# Sheet_1_V2_0_2023-09-05.net
KiCad netlist of a schematic drawn in Altium Designer
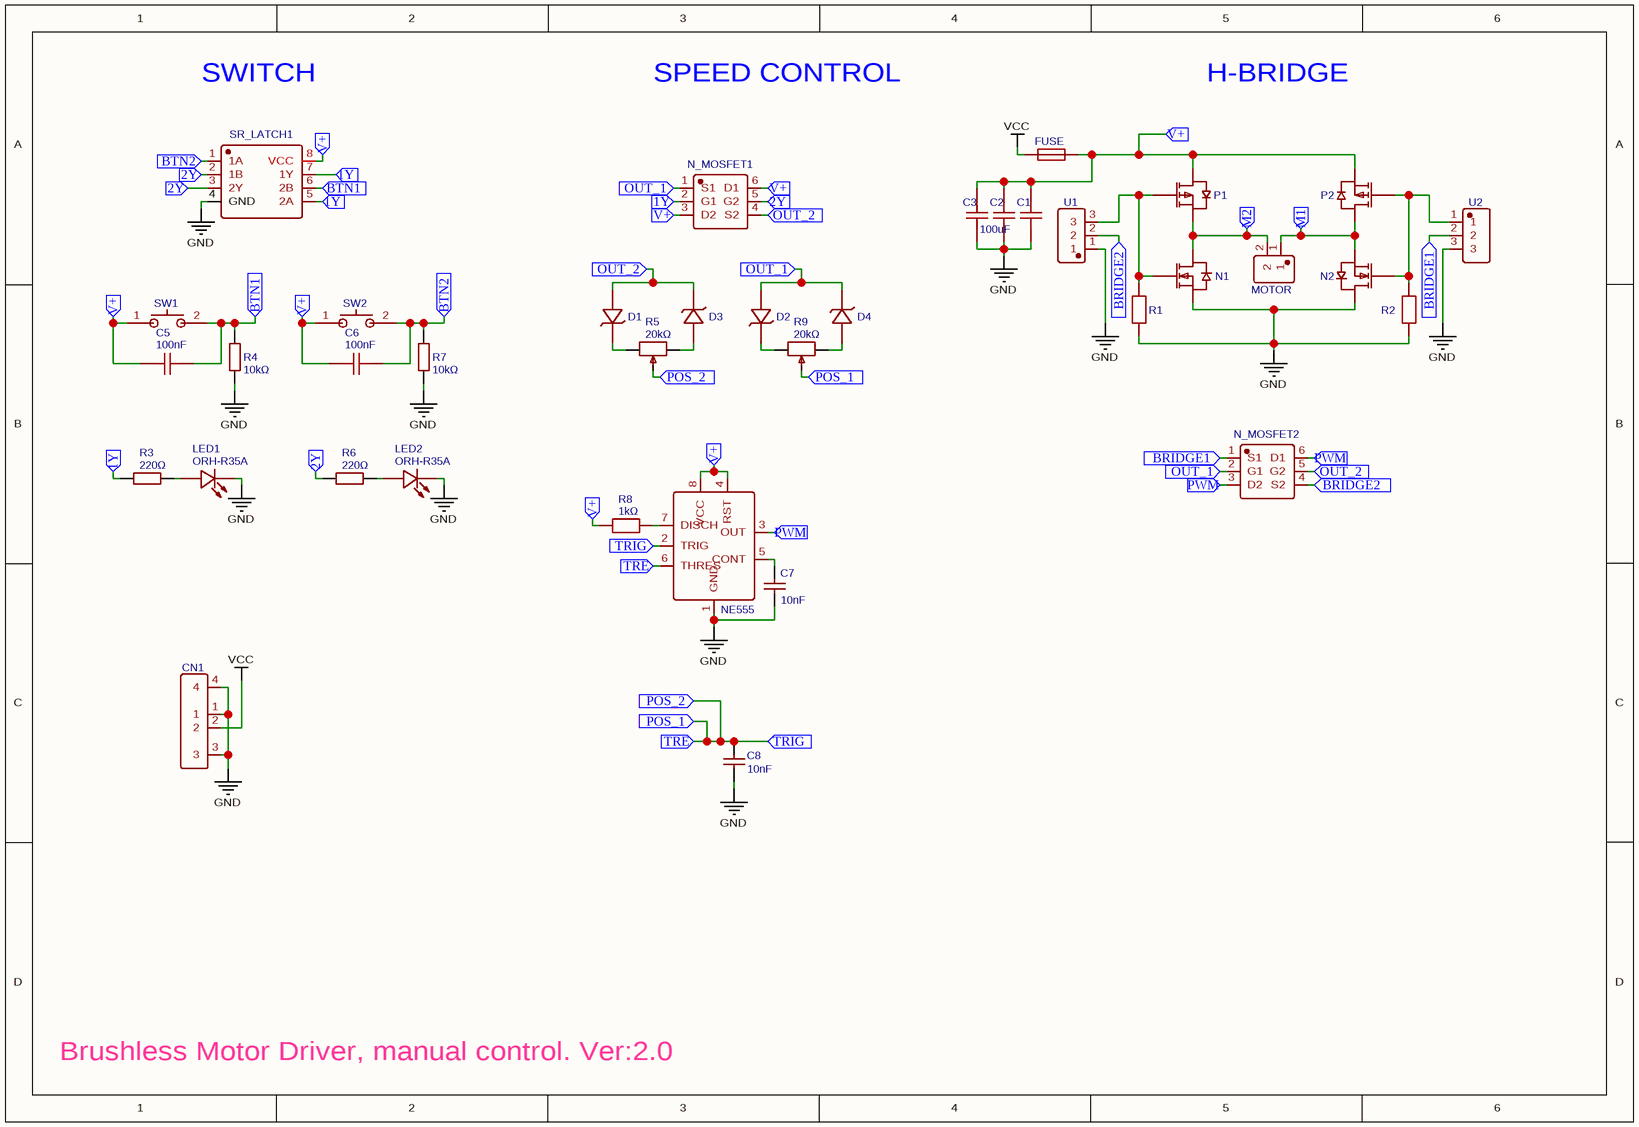
[diagram p0: Sheet_1 V2.0_2023-09-05.schdoc]

(export (version "E")
  (design (tool "Eeschema 10.0.6"))
  (components
    (comp (ref "C1")
      (value "100uF")
      (fields
        (field (name "MANUFACTURER") "muRata(村田)")
        (field (name "MANUFACTURER PART") "GRM31CR61A107MEA8L")
        (field (name "CONTRIBUTOR") "lcsc")
      )
      (libsource (lib "altium-import") (part "root_1_100uF_"))
    )
    (comp (ref "C2")
      (value "100uF")
      (fields
        (field (name "MANUFACTURER") "muRata(村田)")
        (field (name "MANUFACTURER PART") "GRM31CR61A107MEA8L")
        (field (name "CONTRIBUTOR") "lcsc")
      )
      (libsource (lib "altium-import") (part "root_1_100uF_"))
    )
    (comp (ref "C3")
      (value "100uF")
      (fields
        (field (name "MANUFACTURER") "muRata(村田)")
        (field (name "MANUFACTURER PART") "GRM31CR61A107MEA8L")
        (field (name "CONTRIBUTOR") "lcsc")
      )
      (libsource (lib "altium-import") (part "root_1_100uF_"))
    )
    (comp (ref "C5")
      (value "100nF")
      (fields
        (field (name "MANUFACTURER") "SAMSUNG(三星)")
        (field (name "MANUFACTURER PART") "CL10B104KB8NNNC")
      )
      (libsource (lib "altium-import") (part "root_2_100nF_"))
    )
    (comp (ref "C6")
      (value "100nF")
      (fields
        (field (name "MANUFACTURER") "SAMSUNG(三星)")
        (field (name "MANUFACTURER PART") "CL10B104KB8NNNC")
      )
      (libsource (lib "altium-import") (part "root_2_100nF_"))
    )
    (comp (ref "C7")
      (value "10nF")
      (fields (field (name "MANUFACTURER") "FH(风华)") (field (name "MANUFACTURER PART") "1206B103K102NT"))
      (libsource (lib "altium-import") (part "root_1_10nF_"))
    )
    (comp (ref "C8")
      (value "10nF")
      (fields (field (name "MANUFACTURER") "FH(风华)") (field (name "MANUFACTURER PART") "1206B103K102NT"))
      (libsource (lib "altium-import") (part "root_1_10nF_"))
    )
    (comp (ref "CN1")
      (value "SM02B-SRSS-TB (LF)(SN)")
      (fields
        (field (name "MANUFACTURER") "JST")
        (field (name "MANUFACTURER PART") "SM02B-SRSS-TB(LF)(SN)")
        (field (name "CONTRIBUTOR") "LCSC")
      )
      (libsource (lib "altium-import") (part "root_3_SM02B-SRSS-TB (LF)(SN)_"))
    )
    (comp (ref "D1")
      (value "1N4007_C727082")
      (fields
        (field (name "MANUFACTURER") "TWGMC(台湾迪嘉)")
        (field (name "MANUFACTURER PART") "1N4007")
        (field (name "CONTRIBUTOR") "LCSC")
      )
      (libsource (lib "altium-import") (part "root_1_1N4007_C727082_"))
    )
    (comp (ref "D2")
      (value "1N4007_C727082")
      (fields
        (field (name "MANUFACTURER") "TWGMC(台湾迪嘉)")
        (field (name "MANUFACTURER PART") "1N4007")
        (field (name "CONTRIBUTOR") "LCSC")
      )
      (libsource (lib "altium-import") (part "root_1_1N4007_C727082_"))
    )
    (comp (ref "D3")
      (value "1N4007_C727082")
      (fields
        (field (name "MANUFACTURER") "TWGMC(台湾迪嘉)")
        (field (name "MANUFACTURER PART") "1N4007")
        (field (name "CONTRIBUTOR") "LCSC")
      )
      (libsource (lib "altium-import") (part "root_3_1N4007_C727082_"))
    )
    (comp (ref "D4")
      (value "1N4007_C727082")
      (fields
        (field (name "MANUFACTURER") "TWGMC(台湾迪嘉)")
        (field (name "MANUFACTURER PART") "1N4007")
        (field (name "CONTRIBUTOR") "LCSC")
      )
      (libsource (lib "altium-import") (part "root_3_1N4007_C727082_"))
    )
    (comp (ref "FUSE")
      (value "MF-MSMF110/16-2")
      (fields (field (name "MANUFACTURER") "BOURNS") (field (name "CONTRIBUTOR") "LCSC"))
      (libsource (lib "altium-import") (part "root_0_MF-MSMF110/16-2_"))
    )
    (comp (ref "LED1")
      (value "ORH-R35A")
      (fields (field (name "MANUFACTURER") "Orient(奥伦德)") (field (name "CONTRIBUTOR") "LCSC"))
      (libsource (lib "altium-import") (part "root_2_ORH-R35A_"))
    )
    (comp (ref "LED2")
      (value "ORH-R35A")
      (fields (field (name "MANUFACTURER") "Orient(奥伦德)") (field (name "CONTRIBUTOR") "LCSC"))
      (libsource (lib "altium-import") (part "root_2_ORH-R35A_"))
    )
    (comp (ref "MOTOR")
      (value "XH2.54-LI-2P_C2922484")
      (fields (field (name "MANUFACTURER PART") "XH2.54-LI-2P") (field (name "CONTRIBUTOR") "LCSC"))
      (libsource (lib "altium-import") (part "root_3_XH2.54-LI-2P_C2922484_"))
    )
    (comp (ref "N1")
      (value "CJ2302 S2")
      (fields (field (name "MANUFACTURER") "CJ(江苏长电/长晶)"))
      (libsource (lib "altium-import") (part "root_0_CJ2302 S2_"))
    )
    (comp (ref "N2")
      (value "CJ2302 S2")
      (fields (field (name "MANUFACTURER") "CJ(江苏长电/长晶)"))
      (libsource (lib "altium-import") (part "root_2_CJ2302 S2_"))
    )
    (comp (ref "NE555")
      (value "100kHz")
      (fields (field (name "MANUFACTURER") "TI(德州仪器)") (field (name "MANUFACTURER PART") "NE555DR"))
      (libsource (lib "altium-import") (part "root_0_100kHz_"))
    )
    (comp (ref "N_MOSFET1")
      (value "2N7002DWH6327XTSA1")
      (fields
        (field (name "MANUFACTURER") "Infineon(英飞凌)")
        (field (name "MANUFACTURER PART") "2N7002DWH6327")
        (field (name "CONTRIBUTOR") "LCSC")
      )
      (libsource (lib "altium-import") (part "root_0_2N7002DWH6327XTSA1_"))
    )
    (comp (ref "N_MOSFET2")
      (value "2N7002DWH6327XTSA1")
      (fields
        (field (name "MANUFACTURER") "Infineon(英飞凌)")
        (field (name "MANUFACTURER PART") "2N7002DWH6327")
        (field (name "CONTRIBUTOR") "LCSC")
      )
      (libsource (lib "altium-import") (part "root_0_2N7002DWH6327XTSA1_"))
    )
    (comp (ref "P1")
      (value "CJ2301 S1")
      (fields (field (name "MANUFACTURER") "CJ(江苏长电/长晶)"))
      (libsource (lib "altium-import") (part "root_0_CJ2301 S1_"))
    )
    (comp (ref "P2")
      (value "CJ2301 S1")
      (fields (field (name "MANUFACTURER") "CJ(江苏长电/长晶)"))
      (libsource (lib "altium-import") (part "root_2_CJ2301 S1_"))
    )
    (comp (ref "R1")
      (value "1kΩ")
      (fields
        (field (name "MANUFACTURER") "Viking(光颉)")
        (field (name "MANUFACTURER PART") "CR-06JA7----1K")
        (field (name "CONTRIBUTOR") "LCSC")
      )
      (libsource (lib "altium-import") (part "root_1_1kΩ_"))
    )
    (comp (ref "R2")
      (value "1kΩ")
      (fields
        (field (name "MANUFACTURER") "Viking(光颉)")
        (field (name "MANUFACTURER PART") "CR-06JA7----1K")
        (field (name "CONTRIBUTOR") "LCSC")
      )
      (libsource (lib "altium-import") (part "root_1_1kΩ_"))
    )
    (comp (ref "R3")
      (value "220Ω")
      (fields (field (name "MANUFACTURER") "YAGEO(国巨)") (field (name "MANUFACTURER PART") "RC0603FR-07220RL"))
      (libsource (lib "altium-import") (part "root_0_220Ω_"))
    )
    (comp (ref "R4")
      (value "10kΩ")
      (fields
        (field (name "MANUFACTURER") "UNI-ROYAL(厚声)")
        (field (name "MANUFACTURER PART") "0603WAF1002T5E")
      )
      (libsource (lib "altium-import") (part "root_1_10kΩ_"))
    )
    (comp (ref "R5")
      (value "20kΩ")
      (fields (field (name "MANUFACTURER") "HDK(北陆电气)") (field (name "MANUFACTURER PART") "VG039NCHXTB203"))
      (libsource (lib "altium-import") (part "root_1_20kΩ_"))
    )
    (comp (ref "R6")
      (value "220Ω")
      (fields (field (name "MANUFACTURER") "YAGEO(国巨)") (field (name "MANUFACTURER PART") "RC0603FR-07220RL"))
      (libsource (lib "altium-import") (part "root_0_220Ω_"))
    )
    (comp (ref "R7")
      (value "10kΩ")
      (fields
        (field (name "MANUFACTURER") "UNI-ROYAL(厚声)")
        (field (name "MANUFACTURER PART") "0603WAF1002T5E")
      )
      (libsource (lib "altium-import") (part "root_1_10kΩ_"))
    )
    (comp (ref "R8")
      (value "1kΩ")
      (fields
        (field (name "MANUFACTURER") "Viking(光颉)")
        (field (name "MANUFACTURER PART") "CR-06JA7----1K")
        (field (name "CONTRIBUTOR") "LCSC")
      )
      (libsource (lib "altium-import") (part "root_0_1kΩ_"))
    )
    (comp (ref "R9")
      (value "20kΩ")
      (fields (field (name "MANUFACTURER") "HDK(北陆电气)") (field (name "MANUFACTURER PART") "VG039NCHXTB203"))
      (libsource (lib "altium-import") (part "root_1_20kΩ_"))
    )
    (comp (ref "SR_LATCH1")
      (value "SN74LVC2G02DCUR")
      (fields (field (name "MANUFACTURER") "TI(德州仪器)"))
      (libsource (lib "altium-import") (part "root_0_SN74LVC2G02DCUR_"))
    )
    (comp (ref "SW1")
      (value "GT-TC029B-H025-L1N")
      (fields (field (name "MANUFACTURER") "G-Switch(品赞)") (field (name "CONTRIBUTOR") "LCSC"))
      (libsource (lib "altium-import") (part "root_0_GT-TC029B-H025-L1N_"))
    )
    (comp (ref "SW2")
      (value "GT-TC029B-H025-L1N")
      (fields (field (name "MANUFACTURER") "G-Switch(品赞)") (field (name "CONTRIBUTOR") "LCSC"))
      (libsource (lib "altium-import") (part "root_0_GT-TC029B-H025-L1N_"))
    )
    (comp (ref "U1")
      (value "DS1021-1X3SF11-B")
      (fields
        (field (name "MANUFACTURER") "CONNFLY")
        (field (name "MANUFACTURER PART") "DS1021-1x3SF11-B")
        (field (name "CONTRIBUTOR") "lcsc")
      )
      (libsource (lib "altium-import") (part "root_2_DS1021-1X3SF11-B_"))
    )
    (comp (ref "U2")
      (value "DS1021-1X3SF11-B")
      (fields
        (field (name "MANUFACTURER") "CONNFLY")
        (field (name "MANUFACTURER PART") "DS1021-1x3SF11-B")
        (field (name "CONTRIBUTOR") "lcsc")
      )
      (libsource (lib "altium-import") (part "root_0_DS1021-1X3SF11-B_"))
    )
  )
  (nets
    (net (code "1") (name "/1Y") (class "Default")
      (node (ref "N_MOSFET1") (pin "2") (pinfunction "G1_2") (pintype "passive"))
      (node (ref "R3") (pin "1") (pinfunction "1_1") (pintype "passive"))
      (node (ref "SR_LATCH1") (pin "5") (pinfunction "2A_5") (pintype "passive"))
      (node (ref "SR_LATCH1") (pin "7") (pinfunction "1Y_7") (pintype "passive"))
    )
    (net (code "2") (name "/2Y") (class "Default")
      (node (ref "N_MOSFET1") (pin "5") (pinfunction "G2_5") (pintype "passive"))
      (node (ref "R6") (pin "1") (pinfunction "1_1") (pintype "passive"))
      (node (ref "SR_LATCH1") (pin "2") (pinfunction "1B_2") (pintype "passive"))
      (node (ref "SR_LATCH1") (pin "3") (pinfunction "2Y_3") (pintype "passive"))
    )
    (net (code "3") (name "/BRIDGE1") (class "Default")
      (node (ref "N_MOSFET2") (pin "1") (pinfunction "S1_1") (pintype "passive"))
      (node (ref "U2") (pin "2") (pinfunction "2_2") (pintype "passive"))
    )
    (net (code "4") (name "/BRIDGE2") (class "Default")
      (node (ref "N_MOSFET2") (pin "4") (pinfunction "S2_4") (pintype "passive"))
      (node (ref "U1") (pin "2") (pinfunction "2_2") (pintype "passive"))
    )
    (net (code "5") (name "/BTN1") (class "Default")
      (node (ref "C5") (pin "1") (pinfunction "1_1") (pintype "passive"))
      (node (ref "R4") (pin "2") (pinfunction "2_2") (pintype "passive"))
      (node (ref "SR_LATCH1") (pin "6") (pinfunction "2B_6") (pintype "passive"))
      (node (ref "SW1") (pin "2") (pinfunction "2_2") (pintype "passive"))
    )
    (net (code "6") (name "/BTN2") (class "Default")
      (node (ref "C6") (pin "1") (pinfunction "1_1") (pintype "passive"))
      (node (ref "R7") (pin "2") (pinfunction "2_2") (pintype "passive"))
      (node (ref "SR_LATCH1") (pin "1") (pinfunction "1A_1") (pintype "passive"))
      (node (ref "SW2") (pin "2") (pinfunction "2_2") (pintype "passive"))
    )
    (net (code "7") (name "/M1") (class "Default")
      (node (ref "MOTOR") (pin "1") (pinfunction "1_1") (pintype "passive"))
      (node (ref "N2") (pin "2") (pinfunction "S_2") (pintype "passive"))
      (node (ref "P2") (pin "3") (pinfunction "D_3") (pintype "passive"))
    )
    (net (code "8") (name "/M2") (class "Default")
      (node (ref "MOTOR") (pin "2") (pinfunction "2_2") (pintype "passive"))
      (node (ref "N1") (pin "3") (pinfunction "D_3") (pintype "passive"))
      (node (ref "P1") (pin "2") (pinfunction "S_2") (pintype "passive"))
    )
    (net (code "9") (name "/OUT_1") (class "Default")
      (node (ref "D2") (pin "2") (pinfunction "A_2") (pintype "passive"))
      (node (ref "D4") (pin "1") (pinfunction "K_1") (pintype "passive"))
      (node (ref "N_MOSFET1") (pin "1") (pinfunction "S1_1") (pintype "passive"))
      (node (ref "N_MOSFET2") (pin "2") (pinfunction "G1_2") (pintype "passive"))
    )
    (net (code "10") (name "/OUT_2") (class "Default")
      (node (ref "D1") (pin "2") (pinfunction "A_2") (pintype "passive"))
      (node (ref "D3") (pin "1") (pinfunction "K_1") (pintype "passive"))
      (node (ref "N_MOSFET1") (pin "4") (pinfunction "S2_4") (pintype "passive"))
      (node (ref "N_MOSFET2") (pin "5") (pinfunction "G2_5") (pintype "passive"))
    )
    (net (code "11") (name "/POS_1") (class "Default")
      (node (ref "C8") (pin "2") (pinfunction "2_2") (pintype "passive"))
      (node (ref "NE555") (pin "2") (pinfunction "TRIG_2") (pintype "passive"))
      (node (ref "NE555") (pin "6") (pinfunction "THRES_6") (pintype "passive"))
      (node (ref "R5") (pin "2") (pinfunction "2_2") (pintype "passive"))
      (node (ref "R9") (pin "2") (pinfunction "2_2") (pintype "passive"))
    )
    (net (code "12") (name "/PWM") (class "Default")
      (node (ref "NE555") (pin "3") (pinfunction "OUT_3") (pintype "passive"))
      (node (ref "N_MOSFET2") (pin "3") (pinfunction "D2_3") (pintype "passive"))
      (node (ref "N_MOSFET2") (pin "6") (pinfunction "D1_6") (pintype "passive"))
    )
    (net (code "13") (name "/V+") (class "Default")
      (node (ref "C1") (pin "2") (pinfunction "2_2") (pintype "passive"))
      (node (ref "C2") (pin "2") (pinfunction "2_2") (pintype "passive"))
      (node (ref "C3") (pin "2") (pinfunction "2_2") (pintype "passive"))
      (node (ref "C5") (pin "2") (pinfunction "2_2") (pintype "passive"))
      (node (ref "C6") (pin "2") (pinfunction "2_2") (pintype "passive"))
      (node (ref "FUSE") (pin "2") (pinfunction "2_2") (pintype "passive"))
      (node (ref "NE555") (pin "4") (pinfunction "RST_4") (pintype "passive"))
      (node (ref "NE555") (pin "8") (pinfunction "VCC_8") (pintype "passive"))
      (node (ref "N_MOSFET1") (pin "3") (pinfunction "D2_3") (pintype "passive"))
      (node (ref "N_MOSFET1") (pin "6") (pinfunction "D1_6") (pintype "passive"))
      (node (ref "P1") (pin "3") (pinfunction "D_3") (pintype "passive"))
      (node (ref "P2") (pin "2") (pinfunction "S_2") (pintype "passive"))
      (node (ref "R8") (pin "1") (pinfunction "1_1") (pintype "passive"))
      (node (ref "SR_LATCH1") (pin "8") (pinfunction "VCC_8") (pintype "passive"))
      (node (ref "SW1") (pin "1") (pinfunction "1_1") (pintype "passive"))
      (node (ref "SW2") (pin "1") (pinfunction "1_1") (pintype "passive"))
    )
    (net (code "14") (name "GND") (class "Default")
      (node (ref "C1") (pin "1") (pinfunction "1_1") (pintype "passive"))
      (node (ref "C2") (pin "1") (pinfunction "1_1") (pintype "passive"))
      (node (ref "C3") (pin "1") (pinfunction "1_1") (pintype "passive"))
      (node (ref "C7") (pin "1") (pinfunction "1_1") (pintype "passive"))
      (node (ref "C8") (pin "1") (pinfunction "1_1") (pintype "passive"))
      (node (ref "CN1") (pin "1") (pinfunction "1_1") (pintype "passive"))
      (node (ref "CN1") (pin "3") (pinfunction "3_3") (pintype "passive"))
      (node (ref "CN1") (pin "4") (pinfunction "4_4") (pintype "passive"))
      (node (ref "LED1") (pin "2") (pinfunction "C_2") (pintype "passive"))
      (node (ref "LED2") (pin "2") (pinfunction "C_2") (pintype "passive"))
      (node (ref "N1") (pin "2") (pinfunction "S_2") (pintype "passive"))
      (node (ref "N2") (pin "3") (pinfunction "D_3") (pintype "passive"))
      (node (ref "NE555") (pin "1") (pinfunction "GND_1") (pintype "passive"))
      (node (ref "R1") (pin "1") (pinfunction "1_1") (pintype "passive"))
      (node (ref "R2") (pin "1") (pinfunction "1_1") (pintype "passive"))
      (node (ref "R4") (pin "1") (pinfunction "1_1") (pintype "passive"))
      (node (ref "R7") (pin "1") (pinfunction "1_1") (pintype "passive"))
      (node (ref "SR_LATCH1") (pin "4") (pinfunction "GND_4") (pintype "passive"))
      (node (ref "U1") (pin "1") (pinfunction "1_1") (pintype "passive"))
      (node (ref "U2") (pin "3") (pinfunction "3_3") (pintype "passive"))
    )
    (net (code "15") (name "Net-(D1-K)") (class "Default")
      (node (ref "D1") (pin "1") (pinfunction "K_1") (pintype "passive"))
      (node (ref "R5") (pin "3") (pinfunction "3_3") (pintype "passive"))
    )
    (net (code "16") (name "Net-(D2-K)") (class "Default")
      (node (ref "D2") (pin "1") (pinfunction "K_1") (pintype "passive"))
      (node (ref "R9") (pin "3") (pinfunction "3_3") (pintype "passive"))
    )
    (net (code "17") (name "Net-(D3-A)") (class "Default")
      (node (ref "D3") (pin "2") (pinfunction "A_2") (pintype "passive"))
      (node (ref "R5") (pin "1") (pinfunction "1_1") (pintype "passive"))
    )
    (net (code "18") (name "Net-(D4-A)") (class "Default")
      (node (ref "D4") (pin "2") (pinfunction "A_2") (pintype "passive"))
      (node (ref "R9") (pin "1") (pinfunction "1_1") (pintype "passive"))
    )
    (net (code "19") (name "Net-(LED1-A)") (class "Default")
      (node (ref "LED1") (pin "1") (pinfunction "A_1") (pintype "passive"))
      (node (ref "R3") (pin "2") (pinfunction "2_2") (pintype "passive"))
    )
    (net (code "20") (name "Net-(LED2-A)") (class "Default")
      (node (ref "LED2") (pin "1") (pinfunction "A_1") (pintype "passive"))
      (node (ref "R6") (pin "2") (pinfunction "2_2") (pintype "passive"))
    )
    (net (code "21") (name "Net-(N1-G)") (class "Default")
      (node (ref "N1") (pin "1") (pinfunction "G_1") (pintype "passive"))
      (node (ref "P1") (pin "1") (pinfunction "G_1") (pintype "passive"))
      (node (ref "R1") (pin "2") (pinfunction "2_2") (pintype "passive"))
      (node (ref "U1") (pin "3") (pinfunction "3_3") (pintype "passive"))
    )
    (net (code "22") (name "Net-(N2-G)") (class "Default")
      (node (ref "N2") (pin "1") (pinfunction "G_1") (pintype "passive"))
      (node (ref "P2") (pin "1") (pinfunction "G_1") (pintype "passive"))
      (node (ref "R2") (pin "2") (pinfunction "2_2") (pintype "passive"))
      (node (ref "U2") (pin "1") (pinfunction "1_1") (pintype "passive"))
    )
    (net (code "23") (name "Net-(NE555-CONT)") (class "Default")
      (node (ref "C7") (pin "2") (pinfunction "2_2") (pintype "passive"))
      (node (ref "NE555") (pin "5") (pinfunction "CONT_5") (pintype "passive"))
    )
    (net (code "24") (name "Net-(NE555-DISCH)") (class "Default")
      (node (ref "NE555") (pin "7") (pinfunction "DISCH_7") (pintype "passive"))
      (node (ref "R8") (pin "2") (pinfunction "2_2") (pintype "passive"))
    )
    (net (code "25") (name "VCC") (class "Default")
      (node (ref "CN1") (pin "2") (pinfunction "2_2") (pintype "passive"))
      (node (ref "FUSE") (pin "1") (pinfunction "1_1") (pintype "passive"))
    )
  )
)
